# 2_MCU.net
KiCad netlist of a schematic drawn in Altium Designer
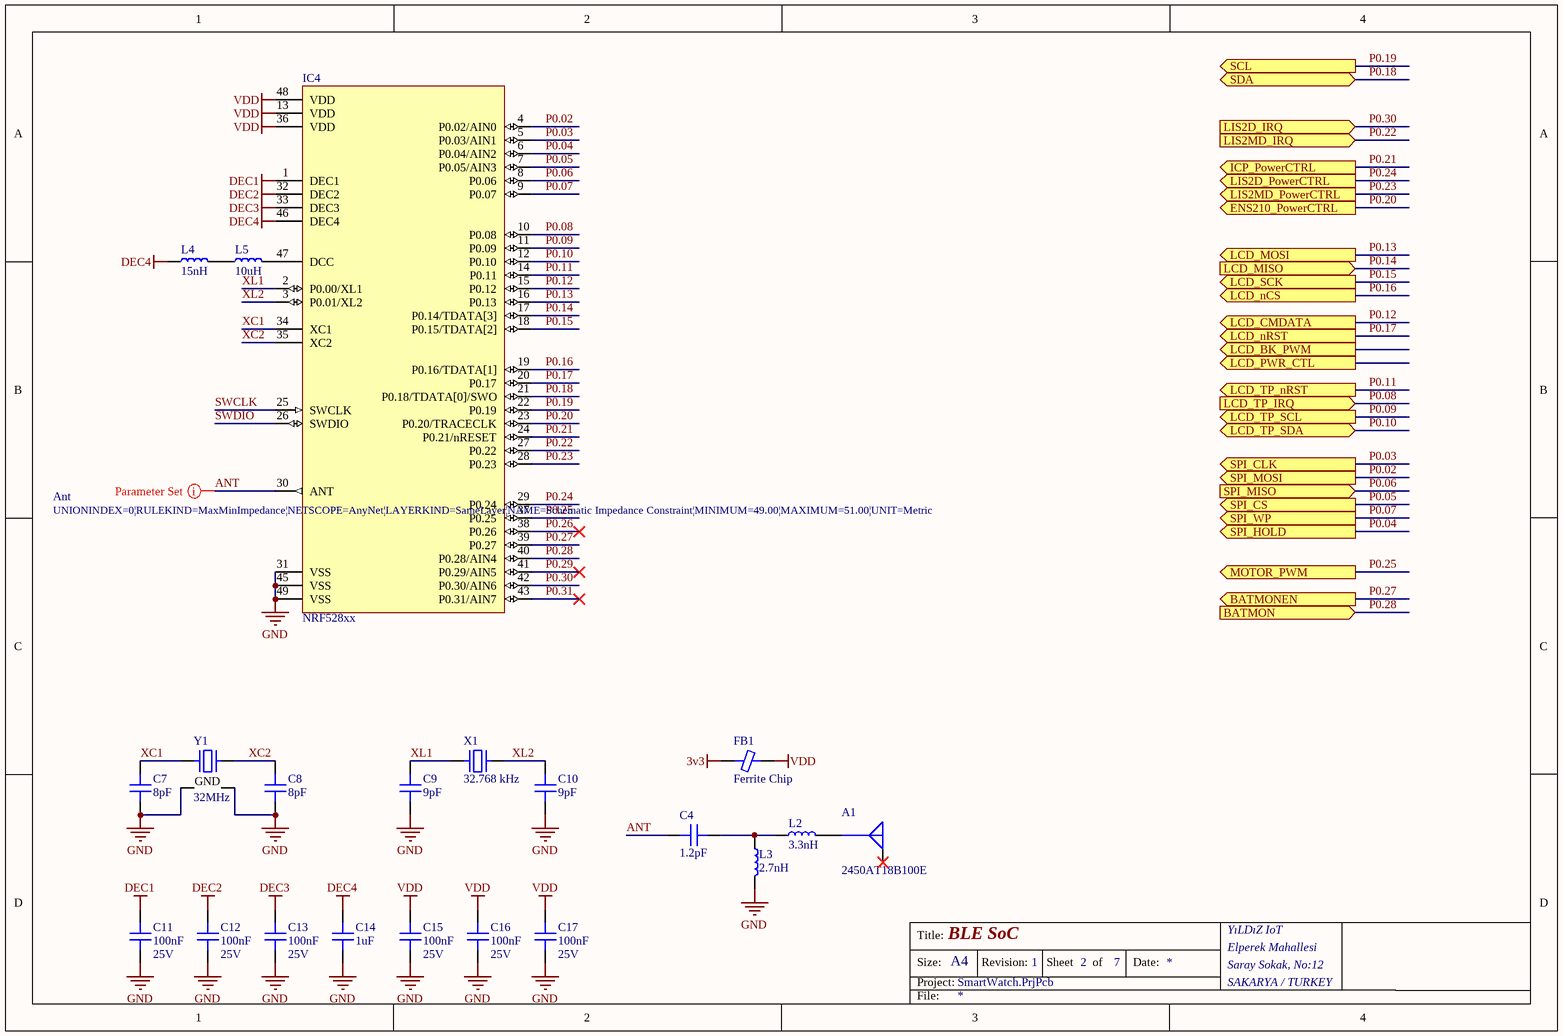
[diagram p0: [2] MCU.SchDoc]

(export (version "E")
  (design (tool "Eeschema 10.0.6"))
  (components
    (comp (ref "A1")
      (value "2450AT18B100E")
      (footprint "ANTC3216X140N")
      (description "Antenna Chip -0.5dBi Gain 2500MHz 2-Pin CSMD T/R")
      (fields (field (name "MANUFACTURER") "Johanson"))
      (libsource (lib "yildizIoT Library") (part "Antenna"))
    )
    (comp (ref "C4")
      (value "1.2pF")
      (footprint "CAP 0402/1005")
      (description "Cap Ceramic 1.2pF 50V C0G 0.1pF SMD 0402 125C Paper T/R")
      (fields
        (field (name "MANUFACTURER") "Johanson")
        (field (name "MANUFACTURER PART NUMBER") "500R07S1R2BV4T")
      )
      (libsource (lib "yildizIoT Library") (part "Capacitor - Ceramic"))
    )
    (comp (ref "C7")
      (value "8pF")
      (footprint "CAP 0402/1005")
      (description "0402 8 pF 50 V ±0.25 pF Tolerance C0G/NP0 Multilayer Ceramic Capacitor")
      (fields
        (field (name "MANUFACTURER") "Murata")
        (field (name "MANUFACTURER PART NUMBER") "GJM1555C1H8R0CB01D")
      )
      (libsource (lib "yildizIoT Library") (part "Capacitor - Ceramic"))
    )
    (comp (ref "C8")
      (value "8pF")
      (footprint "CAP 0402/1005")
      (description "0402 8 pF 50 V ±0.25 pF Tolerance C0G/NP0 Multilayer Ceramic Capacitor")
      (fields
        (field (name "MANUFACTURER") "Murata")
        (field (name "MANUFACTURER PART NUMBER") "GJM1555C1H8R0CB01D")
      )
      (libsource (lib "yildizIoT Library") (part "Capacitor - Ceramic"))
    )
    (comp (ref "C9")
      (value "9pF")
      (footprint "CAP 0402/1005")
      (description "Cap Ceramic 9pF 50V C0G 0.25pF SMD 0402 125°C Paper T/R")
      (fields
        (field (name "MANUFACTURER") "Samsung")
        (field (name "MANUFACTURER PART NUMBER") "CL05C090CB5NNNC")
      )
      (libsource (lib "yildizIoT Library") (part "Capacitor - Ceramic"))
    )
    (comp (ref "C10")
      (value "9pF")
      (footprint "CAP 0402/1005")
      (description "Cap Ceramic 9pF 50V C0G 0.25pF SMD 0402 125°C Paper T/R")
      (fields
        (field (name "MANUFACTURER") "Samsung")
        (field (name "MANUFACTURER PART NUMBER") "CL05C090CB5NNNC")
      )
      (libsource (lib "yildizIoT Library") (part "Capacitor - Ceramic"))
    )
    (comp (ref "C11")
      (value "100nF")
      (footprint "CAP 0402/1005")
      (description "Cap Ceramic 0.1uF 25V X5R 10% Pad SMD 0402 85°C T/R / Multi Layer Ceramic Capacitor (MLCC)")
      (fields
        (field (name "MANUFACTURER") "Samsung")
        (field (name "MANUFACTURER PART NUMBER") "CL05A104KA5NNNC")
        (field (name "VOLTAGE RATING (DC)") "25V")
      )
      (libsource (lib "yildizIoT Library") (part "Capacitor - Ceramic"))
    )
    (comp (ref "C12")
      (value "100nF")
      (footprint "CAP 0402/1005")
      (description "Cap Ceramic 0.1uF 25V X5R 10% Pad SMD 0402 85°C T/R / Multi Layer Ceramic Capacitor (MLCC)")
      (fields
        (field (name "MANUFACTURER") "Samsung")
        (field (name "MANUFACTURER PART NUMBER") "CL05A104KA5NNNC")
        (field (name "VOLTAGE RATING (DC)") "25V")
      )
      (libsource (lib "yildizIoT Library") (part "Capacitor - Ceramic"))
    )
    (comp (ref "C13")
      (value "100nF")
      (footprint "CAP 0402/1005")
      (description "Cap Ceramic 0.1uF 25V X5R 10% Pad SMD 0402 85°C T/R / Multi Layer Ceramic Capacitor (MLCC)")
      (fields
        (field (name "MANUFACTURER") "Samsung")
        (field (name "MANUFACTURER PART NUMBER") "CL05A104KA5NNNC")
        (field (name "VOLTAGE RATING (DC)") "25V")
      )
      (libsource (lib "yildizIoT Library") (part "Capacitor - Ceramic"))
    )
    (comp (ref "C14")
      (value "1uF")
      (footprint "CAP 0402/1005")
      (description "Ceramic capacitor SMD-0402 1000nF /16V X5R# K +-10%, Samsung, RoHS")
      (fields
        (field (name "MANUFACTURER") "Samsung")
        (field (name "MANUFACTURER PART NUMBER") "CL05A105KO5NNNC")
      )
      (libsource (lib "yildizIoT Library") (part "Capacitor - Ceramic"))
    )
    (comp (ref "C15")
      (value "100nF")
      (footprint "CAP 0402/1005")
      (description "Cap Ceramic 0.1uF 25V X5R 10% Pad SMD 0402 85°C T/R / Multi Layer Ceramic Capacitor (MLCC)")
      (fields
        (field (name "MANUFACTURER") "Samsung")
        (field (name "MANUFACTURER PART NUMBER") "CL05A104KA5NNNC")
        (field (name "VOLTAGE RATING (DC)") "25V")
      )
      (libsource (lib "yildizIoT Library") (part "Capacitor - Ceramic"))
    )
    (comp (ref "C16")
      (value "100nF")
      (footprint "CAP 0402/1005")
      (description "Cap Ceramic 0.1uF 25V X5R 10% Pad SMD 0402 85°C T/R / Multi Layer Ceramic Capacitor (MLCC)")
      (fields
        (field (name "MANUFACTURER") "Samsung")
        (field (name "MANUFACTURER PART NUMBER") "CL05A104KA5NNNC")
        (field (name "VOLTAGE RATING (DC)") "25V")
      )
      (libsource (lib "yildizIoT Library") (part "Capacitor - Ceramic"))
    )
    (comp (ref "C17")
      (value "100nF")
      (footprint "CAP 0402/1005")
      (description "Cap Ceramic 0.1uF 25V X5R 10% Pad SMD 0402 85°C T/R / Multi Layer Ceramic Capacitor (MLCC)")
      (fields
        (field (name "MANUFACTURER") "Samsung")
        (field (name "MANUFACTURER PART NUMBER") "CL05A104KA5NNNC")
        (field (name "VOLTAGE RATING (DC)") "25V")
      )
      (libsource (lib "yildizIoT Library") (part "Capacitor - Ceramic"))
    )
    (comp (ref "FB1")
      (value "Ferrite Chip")
      (footprint "FER 0402/1005")
      (description "SMT Ferrite Chip")
      (libsource (lib "yildizIoT Library") (part "Ferrite Chip"))
    )
    (comp (ref "IC4")
      (value "NRF528xx")
      (footprint "QFN40P600X600X90-48N")
      (fields
        (field (name "MANUFACTURER") "Nordic Semiconductor ASA")
        (field (name "MANUFACTURER PART NUMBER") "NRF52832-QFAB-R")
      )
      (libsource (lib "yildizIoT Library") (part "NRF528xx"))
    )
    (comp (ref "L2")
      (value "3.3nH")
      (footprint "IND 0402/1005 RF WW")
      (description "Inductor RF Chip Multi-Layer 0.0033uH 0.3nH 100MHz 8Q-Factor Ceramic 0.3A 0.19Ohm DCR 0402 T/R")
      (fields
        (field (name "MANUFACTURER") "Johanson")
        (field (name "MANUFACTURER PART NUMBER") "L-07C3N3SV6T")
      )
      (libsource (lib "yildizIoT Library") (part "Inductor Air Core"))
    )
    (comp (ref "L3")
      (value "2.7nH")
      (footprint "IND 0402/1005 RF WW")
      (description "Inductor RF Chip Multi-Layer 0.0027uH 0.3nH 100MHz 8Q-Factor Ceramic 0.3A 0.17Ohm DCR 0402 T/R")
      (fields
        (field (name "MANUFACTURER") "Johanson")
        (field (name "MANUFACTURER PART NUMBER") "L-07C2N7SV6T")
      )
      (libsource (lib "yildizIoT Library") (part "Inductor Air Core"))
    )
    (comp (ref "L4")
      (value "15nH")
      (footprint "IND 0402/1005 RF WW")
      (description "Ind High Frequency Chip Multi-Layer 15nH 5% 100MHz 8Q-Factor Ceramic 320mA 0402 T/R")
      (fields
        (field (name "MANUFACTURER") "Taiyo Yuden")
        (field (name "MANUFACTURER PART NUMBER") "HK100515NJ-T")
      )
      (libsource (lib "yildizIoT Library") (part "Inductor Air Core"))
    )
    (comp (ref "L5")
      (value "10uH")
      (footprint "IND 0603/1608 RF")
      (description "Inductor Chip Wirewound 10uH 10% 2.52MHz Ferrite 80mA 468mOhm DCR 0603 T/R")
      (fields
        (field (name "MANUFACTURER") "Taiyo Yuden")
        (field (name "MANUFACTURER PART NUMBER") "LBMF1608T100K")
      )
      (libsource (lib "yildizIoT Library") (part "Inductor Air Core"))
    )
    (comp (ref "X1")
      (value "32.768 kHz")
      (footprint "ABRACON ABS06")
      (description "Crystal 32.7680KHZ 9PF SMD")
      (fields
        (field (name "MANUFACTURER") "Micro Crystal")
        (field (name "MANUFACTURER PART NUMBER") "CM8V-T1A-32.768KHZ-9PF-20PPM-TA-QC")
      )
      (libsource (lib "yildizIoT Library") (part "Abracon Crystal ABS06"))
    )
    (comp (ref "Y1")
      (value "32MHz")
      (footprint "KYOCERA CX2016DB")
      (description "CRYSTAL 32.0000MHZ 8PF SMD")
      (fields
        (field (name "PART NUMBER") "CX2016DB32000D0WZRC1")
        (field (name "MANUFACTURER") "Kyocera International Inc. Electronic Components")
      )
      (libsource (lib "Celestial Altium Library - altium_library") (part "Kyocera Crystal CX2016DB"))
    )
  )
  (nets
    (net (code "1") (name "/ANT") (class "Default")
      (node (ref "C4") (pin "2") (pinfunction "2_2") (pintype "passive"))
      (node (ref "IC4") (pin "30") (pinfunction "ANT_30") (pintype "output"))
    )
    (net (code "4") (name "/P0.02") (class "Default")
      (node (ref "IC4") (pin "4") (pinfunction "P0.02/AIN0_4") (pintype "bidirectional"))
    )
    (net (code "5") (name "/P0.03") (class "Default")
      (node (ref "IC4") (pin "5") (pinfunction "P0.03/AIN1_5") (pintype "bidirectional"))
    )
    (net (code "6") (name "/P0.04") (class "Default")
      (node (ref "IC4") (pin "6") (pinfunction "P0.04/AIN2_6") (pintype "bidirectional"))
    )
    (net (code "7") (name "/P0.05") (class "Default")
      (node (ref "IC4") (pin "7") (pinfunction "P0.05/AIN3_7") (pintype "bidirectional"))
    )
    (net (code "8") (name "/P0.06") (class "Default")
      (node (ref "IC4") (pin "8") (pinfunction "P0.06_8") (pintype "bidirectional"))
    )
    (net (code "9") (name "/P0.07") (class "Default")
      (node (ref "IC4") (pin "9") (pinfunction "P0.07_9") (pintype "bidirectional"))
    )
    (net (code "10") (name "/P0.08") (class "Default")
      (node (ref "IC4") (pin "10") (pinfunction "P0.08_10") (pintype "bidirectional"))
    )
    (net (code "11") (name "/P0.09") (class "Default")
      (node (ref "IC4") (pin "11") (pinfunction "P0.09_11") (pintype "bidirectional"))
    )
    (net (code "12") (name "/P0.10") (class "Default")
      (node (ref "IC4") (pin "12") (pinfunction "P0.10_12") (pintype "bidirectional"))
    )
    (net (code "13") (name "/P0.11") (class "Default")
      (node (ref "IC4") (pin "14") (pinfunction "P0.11_14") (pintype "bidirectional"))
    )
    (net (code "14") (name "/P0.12") (class "Default")
      (node (ref "IC4") (pin "15") (pinfunction "P0.12_15") (pintype "bidirectional"))
    )
    (net (code "15") (name "/P0.13") (class "Default")
      (node (ref "IC4") (pin "16") (pinfunction "P0.13_16") (pintype "bidirectional"))
    )
    (net (code "16") (name "/P0.14") (class "Default")
      (node (ref "IC4") (pin "17") (pinfunction "P0.14/TDATA[3]_17") (pintype "bidirectional"))
    )
    (net (code "17") (name "/P0.15") (class "Default")
      (node (ref "IC4") (pin "18") (pinfunction "P0.15/TDATA[2]_18") (pintype "bidirectional"))
    )
    (net (code "18") (name "/P0.16") (class "Default")
      (node (ref "IC4") (pin "19") (pinfunction "P0.16/TDATA[1]_19") (pintype "bidirectional"))
    )
    (net (code "19") (name "/P0.17") (class "Default")
      (node (ref "IC4") (pin "20") (pinfunction "P0.17_20") (pintype "bidirectional"))
    )
    (net (code "20") (name "/P0.18") (class "Default")
      (node (ref "IC4") (pin "21") (pinfunction "P0.18/TDATA[0]/SWO_21") (pintype "bidirectional"))
    )
    (net (code "21") (name "/P0.19") (class "Default")
      (node (ref "IC4") (pin "22") (pinfunction "P0.19_22") (pintype "bidirectional"))
    )
    (net (code "22") (name "/P0.20") (class "Default")
      (node (ref "IC4") (pin "23") (pinfunction "P0.20/TRACECLK_23") (pintype "bidirectional"))
    )
    (net (code "23") (name "/P0.21") (class "Default")
      (node (ref "IC4") (pin "24") (pinfunction "P0.21/nRESET_24") (pintype "bidirectional"))
    )
    (net (code "24") (name "/P0.22") (class "Default")
      (node (ref "IC4") (pin "27") (pinfunction "P0.22_27") (pintype "bidirectional"))
    )
    (net (code "25") (name "/P0.23") (class "Default")
      (node (ref "IC4") (pin "28") (pinfunction "P0.23_28") (pintype "bidirectional"))
    )
    (net (code "26") (name "/P0.24") (class "Default")
      (node (ref "IC4") (pin "29") (pinfunction "P0.24_29") (pintype "bidirectional"))
    )
    (net (code "27") (name "/P0.25") (class "Default")
      (node (ref "IC4") (pin "37") (pinfunction "P0.25_37") (pintype "bidirectional"))
    )
    (net (code "28") (name "/P0.26") (class "Default")
      (node (ref "IC4") (pin "38") (pinfunction "P0.26_38") (pintype "bidirectional+no_connect"))
    )
    (net (code "29") (name "/P0.27") (class "Default")
      (node (ref "IC4") (pin "39") (pinfunction "P0.27_39") (pintype "bidirectional"))
    )
    (net (code "30") (name "/P0.28") (class "Default")
      (node (ref "IC4") (pin "40") (pinfunction "P0.28/AIN4_40") (pintype "bidirectional"))
    )
    (net (code "31") (name "/P0.29") (class "Default")
      (node (ref "IC4") (pin "41") (pinfunction "P0.29/AIN5_41") (pintype "bidirectional+no_connect"))
    )
    (net (code "32") (name "/P0.30") (class "Default")
      (node (ref "IC4") (pin "42") (pinfunction "P0.30/AIN6_42") (pintype "bidirectional"))
    )
    (net (code "33") (name "/P0.31") (class "Default")
      (node (ref "IC4") (pin "43") (pinfunction "P0.31/AIN7_43") (pintype "bidirectional+no_connect"))
    )
    (net (code "34") (name "/SWCLK") (class "Default")
      (node (ref "IC4") (pin "25") (pinfunction "SWCLK_25") (pintype "input"))
    )
    (net (code "35") (name "/SWDIO") (class "Default")
      (node (ref "IC4") (pin "26") (pinfunction "SWDIO_26") (pintype "bidirectional"))
    )
    (net (code "36") (name "/XC1") (class "Default")
      (node (ref "C7") (pin "2") (pinfunction "2_2") (pintype "passive"))
      (node (ref "IC4") (pin "34") (pinfunction "XC1_34") (pintype "power_in"))
      (node (ref "Y1") (pin "1") (pinfunction "1_1") (pintype "passive"))
    )
    (net (code "37") (name "/XC2") (class "Default")
      (node (ref "C8") (pin "2") (pinfunction "2_2") (pintype "passive"))
      (node (ref "IC4") (pin "35") (pinfunction "XC2_35") (pintype "passive"))
      (node (ref "Y1") (pin "3") (pinfunction "3_3") (pintype "passive"))
    )
    (net (code "38") (name "/XL1") (class "Default")
      (node (ref "C9") (pin "2") (pinfunction "2_2") (pintype "passive"))
      (node (ref "IC4") (pin "2") (pinfunction "P0.00/XL1_2") (pintype "bidirectional"))
      (node (ref "X1") (pin "1") (pinfunction "1_1") (pintype "passive"))
    )
    (net (code "39") (name "/XL2") (class "Default")
      (node (ref "C10") (pin "2") (pinfunction "2_2") (pintype "passive"))
      (node (ref "IC4") (pin "3") (pinfunction "P0.01/XL2_3") (pintype "bidirectional"))
      (node (ref "X1") (pin "2") (pinfunction "2_2") (pintype "passive"))
    )
    (net (code "40") (name "3v3") (class "Default")
      (node (ref "FB1") (pin "1") (pinfunction "1_1") (pintype "passive"))
    )
    (net (code "41") (name "DEC1") (class "Default")
      (node (ref "C11") (pin "2") (pinfunction "2_2") (pintype "passive"))
      (node (ref "IC4") (pin "1") (pinfunction "DEC1_1") (pintype "power_in"))
    )
    (net (code "42") (name "DEC2") (class "Default")
      (node (ref "C12") (pin "2") (pinfunction "2_2") (pintype "passive"))
      (node (ref "IC4") (pin "32") (pinfunction "DEC2_32") (pintype "power_in"))
    )
    (net (code "43") (name "DEC3") (class "Default")
      (node (ref "C13") (pin "2") (pinfunction "2_2") (pintype "passive"))
      (node (ref "IC4") (pin "33") (pinfunction "DEC3_33") (pintype "power_in"))
    )
    (net (code "44") (name "DEC4") (class "Default")
      (node (ref "C14") (pin "2") (pinfunction "2_2") (pintype "passive"))
      (node (ref "IC4") (pin "46") (pinfunction "DEC4_46") (pintype "power_in"))
      (node (ref "L4") (pin "1") (pinfunction "1_1") (pintype "passive"))
    )
    (net (code "45") (name "GND") (class "Default")
      (node (ref "C10") (pin "1") (pinfunction "1_1") (pintype "passive"))
      (node (ref "C11") (pin "1") (pinfunction "1_1") (pintype "passive"))
      (node (ref "C12") (pin "1") (pinfunction "1_1") (pintype "passive"))
      (node (ref "C13") (pin "1") (pinfunction "1_1") (pintype "passive"))
      (node (ref "C14") (pin "1") (pinfunction "1_1") (pintype "passive"))
      (node (ref "C15") (pin "1") (pinfunction "1_1") (pintype "passive"))
      (node (ref "C16") (pin "1") (pinfunction "1_1") (pintype "passive"))
      (node (ref "C17") (pin "1") (pinfunction "1_1") (pintype "passive"))
      (node (ref "C7") (pin "1") (pinfunction "1_1") (pintype "passive"))
      (node (ref "C8") (pin "1") (pinfunction "1_1") (pintype "passive"))
      (node (ref "C9") (pin "1") (pinfunction "1_1") (pintype "passive"))
      (node (ref "IC4") (pin "31") (pinfunction "VSS_31") (pintype "power_in"))
      (node (ref "IC4") (pin "45") (pinfunction "VSS_45") (pintype "power_in"))
      (node (ref "IC4") (pin "49") (pinfunction "VSS_49") (pintype "power_in"))
      (node (ref "L3") (pin "2") (pinfunction "2_2") (pintype "passive"))
      (node (ref "Y1") (pin "2") (pinfunction "GND_2") (pintype "passive"))
      (node (ref "Y1") (pin "4") (pinfunction "GND_4") (pintype "passive"))
    )
    (net (code "46") (name "Net-(A1-PadS)") (class "Default")
      (node (ref "A1") (pin "S") (pinfunction "S_S") (pintype "passive"))
      (node (ref "L2") (pin "2") (pinfunction "2_2") (pintype "passive"))
    )
    (net (code "47") (name "Net-(C4-Pad1)") (class "Default")
      (node (ref "C4") (pin "1") (pinfunction "1_1") (pintype "passive"))
      (node (ref "L2") (pin "1") (pinfunction "1_1") (pintype "passive"))
      (node (ref "L3") (pin "1") (pinfunction "1_1") (pintype "passive"))
    )
    (net (code "48") (name "Net-(IC4-DCC)") (class "Default")
      (node (ref "IC4") (pin "47") (pinfunction "DCC_47") (pintype "power_in"))
      (node (ref "L5") (pin "2") (pinfunction "2_2") (pintype "passive"))
    )
    (net (code "49") (name "Net-(L4-Pad2)") (class "Default")
      (node (ref "L4") (pin "2") (pinfunction "2_2") (pintype "passive"))
      (node (ref "L5") (pin "1") (pinfunction "1_1") (pintype "passive"))
    )
    (net (code "50") (name "VDD") (class "Default")
      (node (ref "C15") (pin "2") (pinfunction "2_2") (pintype "passive"))
      (node (ref "C16") (pin "2") (pinfunction "2_2") (pintype "passive"))
      (node (ref "C17") (pin "2") (pinfunction "2_2") (pintype "passive"))
      (node (ref "FB1") (pin "2") (pinfunction "2_2") (pintype "passive"))
      (node (ref "IC4") (pin "13") (pinfunction "VDD_13") (pintype "power_in"))
      (node (ref "IC4") (pin "36") (pinfunction "VDD_36") (pintype "power_in"))
      (node (ref "IC4") (pin "48") (pinfunction "VDD_48") (pintype "power_in"))
    )
    (net (code "51") (name "unconnected-(A1-PadG)") (class "Default")
      (node (ref "A1") (pin "G") (pinfunction "G_G") (pintype "passive+no_connect"))
    )
    (net (code "52") (name "unconnected-(IC4-NC-Pad44)") (class "Default")
      (node (ref "IC4") (pin "44") (pinfunction "NC_44") (pintype "passive"))
    )
  )
)
